# schematic.net
KiCad netlist of a schematic drawn in Altium Designer
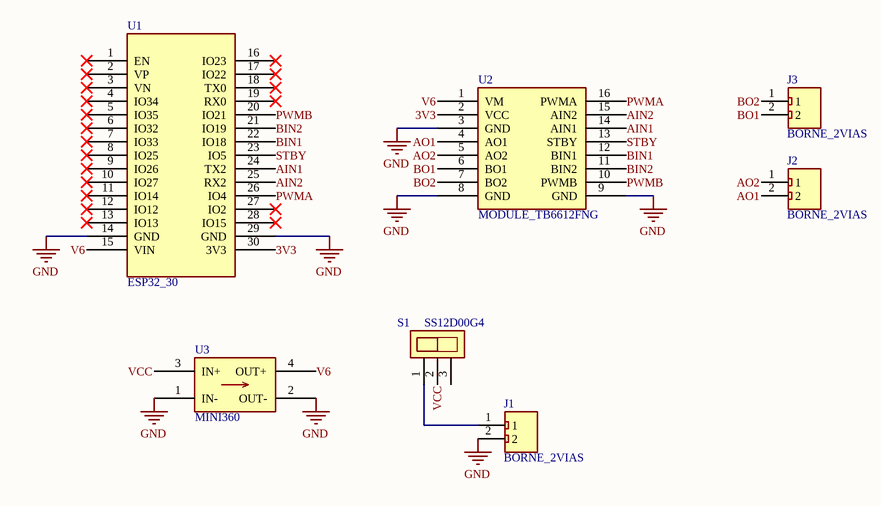
[diagram p0: schematic.SchDoc]

(export (version "E")
  (design (tool "Eeschema 10.0.6"))
  (components
    (comp (ref "J1")
      (value "BORNE_2VIAS")
      (footprint "BORNE_2_VIAS")
      (libsource (lib "Connectors") (part "BORNE_2VIAS"))
    )
    (comp (ref "J2")
      (value "BORNE_2VIAS")
      (footprint "BORNE_2_VIAS")
      (libsource (lib "Connectors") (part "BORNE_2VIAS"))
    )
    (comp (ref "J3")
      (value "BORNE_2VIAS")
      (footprint "BORNE_2_VIAS")
      (libsource (lib "Connectors") (part "BORNE_2VIAS"))
    )
    (comp (ref "S1")
      (value "SS12D00G4")
      (footprint "SS12D00G4")
      (libsource (lib "Buttons & Switches") (part "SS12D00G4"))
    )
    (comp (ref "U1")
      (value "ESP32_30")
      (footprint "ESP32_30")
      (description "Microcontoller Board 30 Pins Wifi 2.4GHz BLE 4.2 ESP32-WROOM-32D")
      (libsource (lib "Espressif Microcontrollers") (part "ESP32_30"))
    )
    (comp (ref "U2")
      (value "MODULE_TB6612FNG")
      (footprint "MODULE_TB6612FNG")
      (description "Module Dual Motor Driver 2.5-13.5V 3.2A Peak 21x18mm")
      (libsource (lib "Motor Drivers") (part "MODULE_TB6612FNG"))
    )
    (comp (ref "U3")
      (value "MINI360")
      (footprint "MINI360")
      (description "MODULE BUCK STEP DOWN 3A 18x12mm")
      (libsource (lib "Voltage Regulators") (part "MINI360"))
    )
  )
  (nets
    (net (code "1") (name "/3V3") (class "Default")
      (node (ref "U1") (pin "30") (pinfunction "3V3_30") (pintype "passive"))
      (node (ref "U2") (pin "2") (pinfunction "VCC_2") (pintype "passive"))
    )
    (net (code "2") (name "/AIN1") (class "Default")
      (node (ref "U1") (pin "24") (pinfunction "TX2_24") (pintype "passive"))
      (node (ref "U2") (pin "14") (pinfunction "AIN1_14") (pintype "passive"))
    )
    (net (code "3") (name "/AIN2") (class "Default")
      (node (ref "U1") (pin "25") (pinfunction "RX2_25") (pintype "passive"))
      (node (ref "U2") (pin "15") (pinfunction "AIN2_15") (pintype "passive"))
    )
    (net (code "4") (name "/AO1") (class "Default")
      (node (ref "J2") (pin "2") (pinfunction "2_2") (pintype "passive"))
      (node (ref "U2") (pin "4") (pinfunction "AO1_4") (pintype "passive"))
    )
    (net (code "5") (name "/AO2") (class "Default")
      (node (ref "J2") (pin "1") (pinfunction "1_1") (pintype "passive"))
      (node (ref "U2") (pin "5") (pinfunction "AO2_5") (pintype "passive"))
    )
    (net (code "6") (name "/BIN1") (class "Default")
      (node (ref "U1") (pin "22") (pinfunction "IO18_22") (pintype "passive"))
      (node (ref "U2") (pin "12") (pinfunction "BIN1_12") (pintype "passive"))
    )
    (net (code "7") (name "/BIN2") (class "Default")
      (node (ref "U1") (pin "21") (pinfunction "IO19_21") (pintype "passive"))
      (node (ref "U2") (pin "11") (pinfunction "BIN2_11") (pintype "passive"))
    )
    (net (code "8") (name "/BO1") (class "Default")
      (node (ref "J3") (pin "2") (pinfunction "2_2") (pintype "passive"))
      (node (ref "U2") (pin "6") (pinfunction "BO1_6") (pintype "passive"))
    )
    (net (code "9") (name "/BO2") (class "Default")
      (node (ref "J3") (pin "1") (pinfunction "1_1") (pintype "passive"))
      (node (ref "U2") (pin "7") (pinfunction "BO2_7") (pintype "passive"))
    )
    (net (code "10") (name "/PWMA") (class "Default")
      (node (ref "U1") (pin "26") (pinfunction "IO4_26") (pintype "passive"))
      (node (ref "U2") (pin "16") (pinfunction "PWMA_16") (pintype "passive"))
    )
    (net (code "11") (name "/PWMB") (class "Default")
      (node (ref "U1") (pin "20") (pinfunction "IO21_20") (pintype "passive"))
      (node (ref "U2") (pin "10") (pinfunction "PWMB_10") (pintype "passive"))
    )
    (net (code "12") (name "/STBY") (class "Default")
      (node (ref "U1") (pin "23") (pinfunction "IO5_23") (pintype "passive"))
      (node (ref "U2") (pin "13") (pinfunction "STBY_13") (pintype "passive"))
    )
    (net (code "13") (name "/V6") (class "Default")
      (node (ref "U1") (pin "15") (pinfunction "VIN_15") (pintype "passive"))
      (node (ref "U2") (pin "1") (pinfunction "VM_1") (pintype "passive"))
      (node (ref "U3") (pin "4") (pinfunction "OUT+_4") (pintype "passive"))
    )
    (net (code "14") (name "/VCC") (class "Default")
      (node (ref "S1") (pin "2") (pintype "passive"))
      (node (ref "U3") (pin "3") (pinfunction "IN+_3") (pintype "passive"))
    )
    (net (code "15") (name "GND") (class "Default")
      (node (ref "J1") (pin "2") (pinfunction "2_2") (pintype "passive"))
      (node (ref "U1") (pin "14") (pinfunction "GND_14") (pintype "passive"))
      (node (ref "U1") (pin "29") (pinfunction "GND_29") (pintype "passive"))
      (node (ref "U2") (pin "3") (pinfunction "GND_3") (pintype "passive"))
      (node (ref "U2") (pin "8") (pinfunction "GND_8") (pintype "passive"))
      (node (ref "U2") (pin "9") (pinfunction "GND_9") (pintype "passive"))
      (node (ref "U3") (pin "1") (pinfunction "IN-_1") (pintype "passive"))
      (node (ref "U3") (pin "2") (pinfunction "OUT-_2") (pintype "passive"))
    )
    (net (code "16") (name "Net-(J1-Pad1)") (class "Default")
      (node (ref "J1") (pin "1") (pinfunction "1_1") (pintype "passive"))
      (node (ref "S1") (pin "1") (pintype "passive"))
    )
    (net (code "17") (name "unconnected-(S1-Pad3)") (class "Default")
      (node (ref "S1") (pin "3") (pintype "passive"))
    )
    (net (code "18") (name "unconnected-(U1-EN-Pad1)") (class "Default")
      (node (ref "U1") (pin "1") (pinfunction "EN_1") (pintype "passive+no_connect"))
    )
    (net (code "19") (name "unconnected-(U1-IO2-Pad27)") (class "Default")
      (node (ref "U1") (pin "27") (pinfunction "IO2_27") (pintype "passive+no_connect"))
    )
    (net (code "20") (name "unconnected-(U1-IO12-Pad12)") (class "Default")
      (node (ref "U1") (pin "12") (pinfunction "IO12_12") (pintype "passive+no_connect"))
    )
    (net (code "21") (name "unconnected-(U1-IO13-Pad13)") (class "Default")
      (node (ref "U1") (pin "13") (pinfunction "IO13_13") (pintype "passive+no_connect"))
    )
    (net (code "22") (name "unconnected-(U1-IO14-Pad11)") (class "Default")
      (node (ref "U1") (pin "11") (pinfunction "IO14_11") (pintype "passive+no_connect"))
    )
    (net (code "23") (name "unconnected-(U1-IO15-Pad28)") (class "Default")
      (node (ref "U1") (pin "28") (pinfunction "IO15_28") (pintype "passive+no_connect"))
    )
    (net (code "24") (name "unconnected-(U1-IO22-Pad17)") (class "Default")
      (node (ref "U1") (pin "17") (pinfunction "IO22_17") (pintype "passive+no_connect"))
    )
    (net (code "25") (name "unconnected-(U1-IO23-Pad16)") (class "Default")
      (node (ref "U1") (pin "16") (pinfunction "IO23_16") (pintype "passive+no_connect"))
    )
    (net (code "26") (name "unconnected-(U1-IO25-Pad8)") (class "Default")
      (node (ref "U1") (pin "8") (pinfunction "IO25_8") (pintype "passive+no_connect"))
    )
    (net (code "27") (name "unconnected-(U1-IO26-Pad9)") (class "Default")
      (node (ref "U1") (pin "9") (pinfunction "IO26_9") (pintype "passive+no_connect"))
    )
    (net (code "28") (name "unconnected-(U1-IO27-Pad10)") (class "Default")
      (node (ref "U1") (pin "10") (pinfunction "IO27_10") (pintype "passive+no_connect"))
    )
    (net (code "29") (name "unconnected-(U1-IO32-Pad6)") (class "Default")
      (node (ref "U1") (pin "6") (pinfunction "IO32_6") (pintype "passive+no_connect"))
    )
    (net (code "30") (name "unconnected-(U1-IO33-Pad7)") (class "Default")
      (node (ref "U1") (pin "7") (pinfunction "IO33_7") (pintype "passive+no_connect"))
    )
    (net (code "31") (name "unconnected-(U1-IO34-Pad4)") (class "Default")
      (node (ref "U1") (pin "4") (pinfunction "IO34_4") (pintype "passive+no_connect"))
    )
    (net (code "32") (name "unconnected-(U1-IO35-Pad5)") (class "Default")
      (node (ref "U1") (pin "5") (pinfunction "IO35_5") (pintype "passive+no_connect"))
    )
    (net (code "33") (name "unconnected-(U1-RX0-Pad19)") (class "Default")
      (node (ref "U1") (pin "19") (pinfunction "RX0_19") (pintype "passive+no_connect"))
    )
    (net (code "34") (name "unconnected-(U1-TX0-Pad18)") (class "Default")
      (node (ref "U1") (pin "18") (pinfunction "TX0_18") (pintype "passive+no_connect"))
    )
    (net (code "35") (name "unconnected-(U1-VN-Pad3)") (class "Default")
      (node (ref "U1") (pin "3") (pinfunction "VN_3") (pintype "passive+no_connect"))
    )
    (net (code "36") (name "unconnected-(U1-VP-Pad2)") (class "Default")
      (node (ref "U1") (pin "2") (pinfunction "VP_2") (pintype "passive+no_connect"))
    )
  )
)
